# CursorKeypad.net
KiCad netlist of a schematic drawn in EAGLE
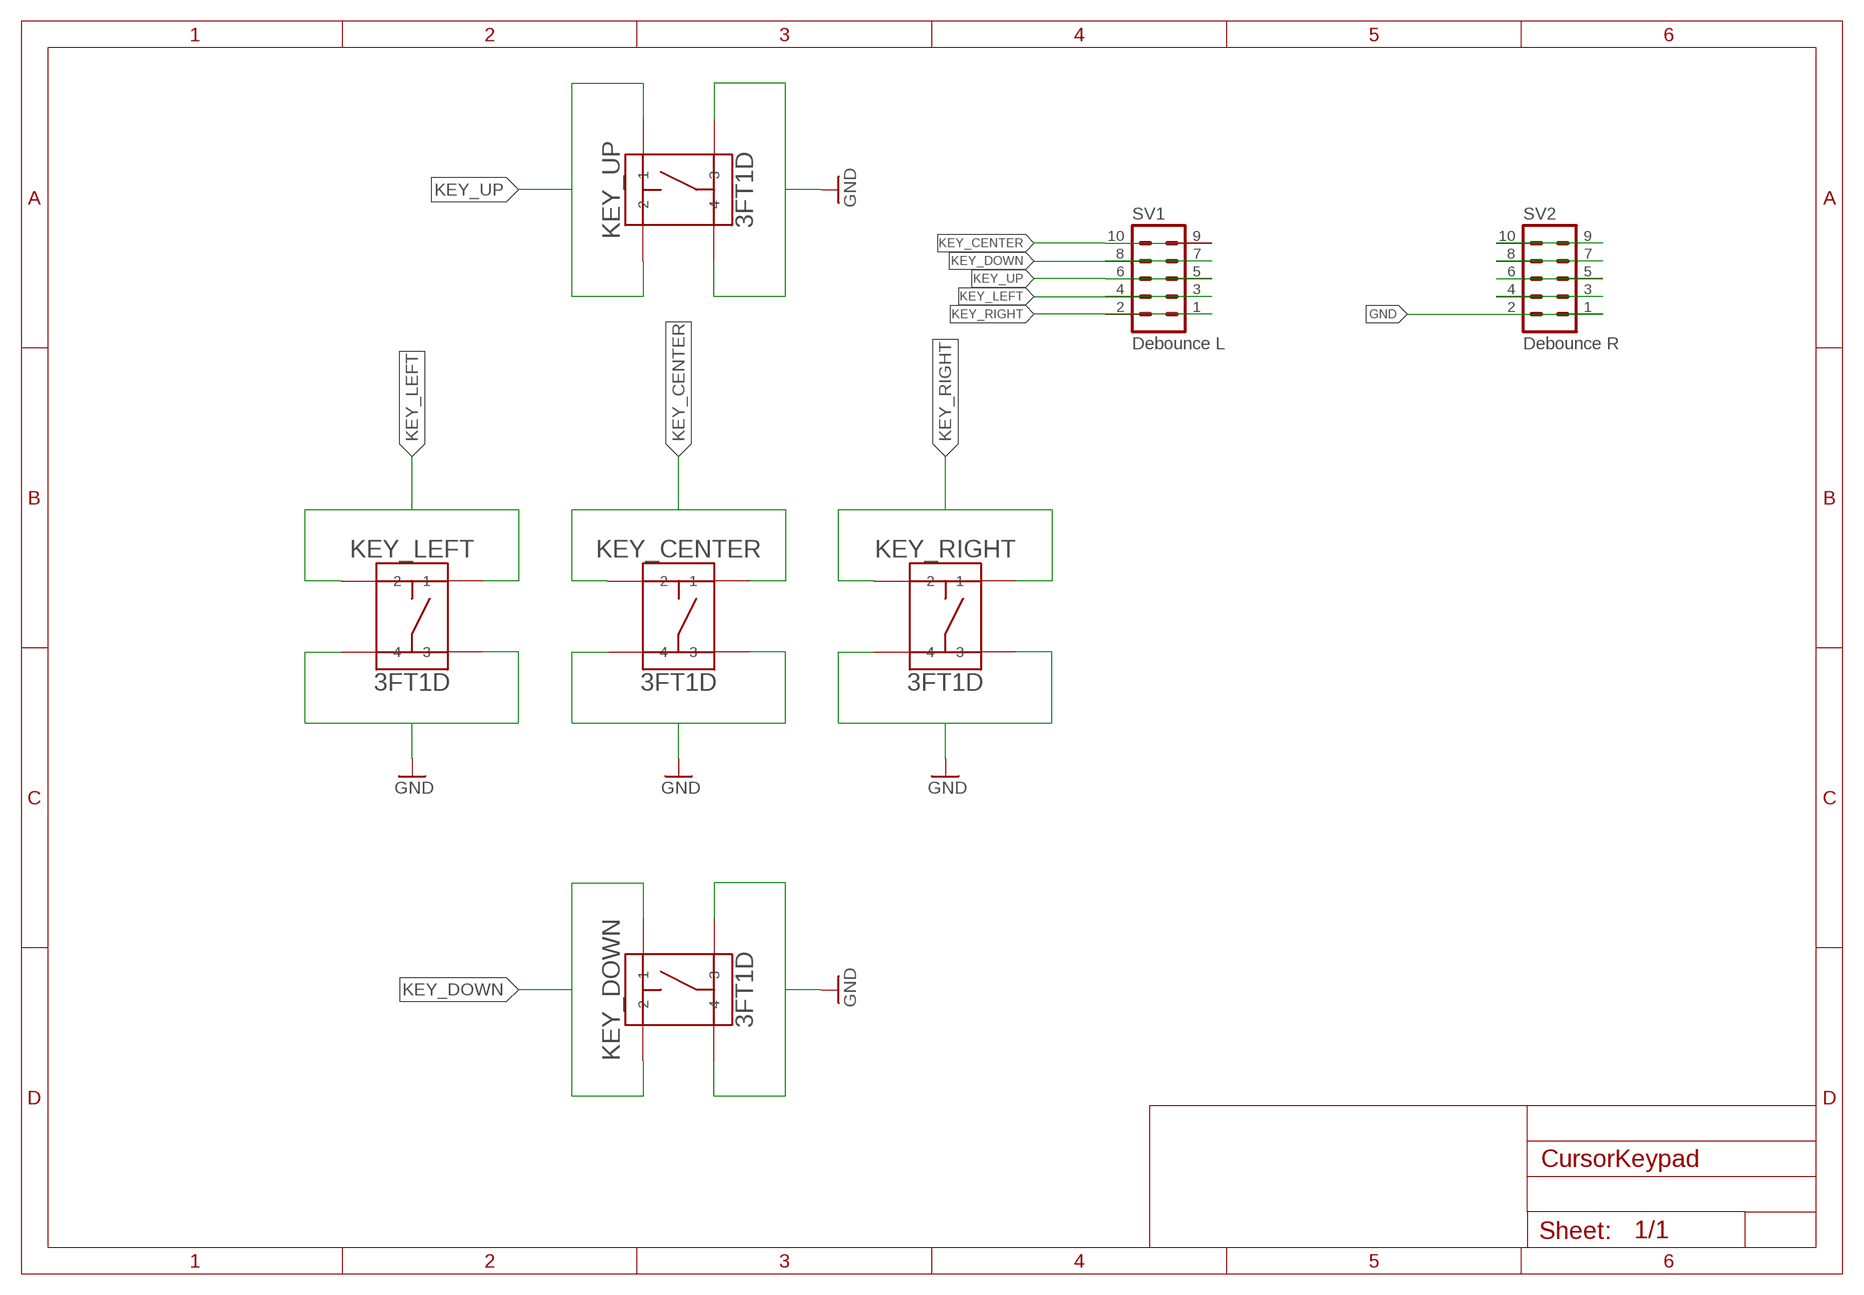
[diagram p0: schematic, sheet 1]

(export (version "E")
  (design (tool "Eeschema 10.0.6"))
  (components
    (comp (ref "KEY_CENTER")
      (value "3FT1D")
      (footprint "eagle-import:3FT")
      (libsource (lib "eagle-import") (part "3FT1D"))
    )
    (comp (ref "KEY_DOWN")
      (value "3FT1D")
      (footprint "eagle-import:3FT")
      (libsource (lib "eagle-import") (part "3FT1D"))
    )
    (comp (ref "KEY_LEFT")
      (value "3FT1D")
      (footprint "eagle-import:3FT")
      (libsource (lib "eagle-import") (part "3FT1D"))
    )
    (comp (ref "KEY_RIGHT")
      (value "3FT1D")
      (footprint "eagle-import:3FT")
      (libsource (lib "eagle-import") (part "3FT1D"))
    )
    (comp (ref "KEY_UP")
      (value "3FT1D")
      (footprint "eagle-import:3FT")
      (libsource (lib "eagle-import") (part "3FT1D"))
    )
    (comp (ref "SV1")
      (value "Debounce L")
      (footprint "eagle-import:MA05-2")
      (libsource (lib "eagle-import") (part "MA05-2"))
    )
    (comp (ref "SV2")
      (value "Debounce R")
      (footprint "eagle-import:MA05-2")
      (libsource (lib "eagle-import") (part "MA05-2"))
    )
  )
  (nets
    (net (code "1") (name "GND") (class "Default")
      (node (ref "KEY_CENTER") (pin "P$3") (pinfunction "3_P$3") (pintype "bidirectional"))
      (node (ref "KEY_CENTER") (pin "P$4") (pinfunction "4_P$4") (pintype "bidirectional"))
      (node (ref "KEY_DOWN") (pin "P$3") (pinfunction "3_P$3") (pintype "bidirectional"))
      (node (ref "KEY_DOWN") (pin "P$4") (pinfunction "4_P$4") (pintype "bidirectional"))
      (node (ref "KEY_LEFT") (pin "P$3") (pinfunction "3_P$3") (pintype "bidirectional"))
      (node (ref "KEY_LEFT") (pin "P$4") (pinfunction "4_P$4") (pintype "bidirectional"))
      (node (ref "KEY_RIGHT") (pin "P$3") (pinfunction "3_P$3") (pintype "bidirectional"))
      (node (ref "KEY_RIGHT") (pin "P$4") (pinfunction "4_P$4") (pintype "bidirectional"))
      (node (ref "KEY_UP") (pin "P$3") (pinfunction "3_P$3") (pintype "bidirectional"))
      (node (ref "KEY_UP") (pin "P$4") (pinfunction "4_P$4") (pintype "bidirectional"))
      (node (ref "SV2") (pin "1") (pinfunction "1_1") (pintype "passive"))
      (node (ref "SV2") (pin "2") (pinfunction "2_2") (pintype "passive"))
    )
    (net (code "2") (name "KEY_CENTER") (class "Default")
      (node (ref "KEY_CENTER") (pin "P$1") (pinfunction "1_P$1") (pintype "bidirectional"))
      (node (ref "KEY_CENTER") (pin "P$2") (pinfunction "2_P$2") (pintype "bidirectional"))
      (node (ref "SV1") (pin "10") (pinfunction "10_10") (pintype "passive"))
      (node (ref "SV1") (pin "9") (pinfunction "9_9") (pintype "passive"))
    )
    (net (code "3") (name "KEY_DOWN") (class "Default")
      (node (ref "KEY_DOWN") (pin "P$1") (pinfunction "1_P$1") (pintype "bidirectional"))
      (node (ref "KEY_DOWN") (pin "P$2") (pinfunction "2_P$2") (pintype "bidirectional"))
      (node (ref "SV1") (pin "7") (pinfunction "7_7") (pintype "passive"))
      (node (ref "SV1") (pin "8") (pinfunction "8_8") (pintype "passive"))
    )
    (net (code "4") (name "KEY_LEFT") (class "Default")
      (node (ref "KEY_LEFT") (pin "P$1") (pinfunction "1_P$1") (pintype "bidirectional"))
      (node (ref "KEY_LEFT") (pin "P$2") (pinfunction "2_P$2") (pintype "bidirectional"))
      (node (ref "SV1") (pin "3") (pinfunction "3_3") (pintype "passive"))
      (node (ref "SV1") (pin "4") (pinfunction "4_4") (pintype "passive"))
    )
    (net (code "5") (name "KEY_RIGHT") (class "Default")
      (node (ref "KEY_RIGHT") (pin "P$1") (pinfunction "1_P$1") (pintype "bidirectional"))
      (node (ref "KEY_RIGHT") (pin "P$2") (pinfunction "2_P$2") (pintype "bidirectional"))
      (node (ref "SV1") (pin "1") (pinfunction "1_1") (pintype "passive"))
      (node (ref "SV1") (pin "2") (pinfunction "2_2") (pintype "passive"))
    )
    (net (code "6") (name "KEY_UP") (class "Default")
      (node (ref "KEY_UP") (pin "P$1") (pinfunction "1_P$1") (pintype "bidirectional"))
      (node (ref "KEY_UP") (pin "P$2") (pinfunction "2_P$2") (pintype "bidirectional"))
      (node (ref "SV1") (pin "5") (pinfunction "5_5") (pintype "passive"))
      (node (ref "SV1") (pin "6") (pinfunction "6_6") (pintype "passive"))
    )
    (net (code "7") (name "Net-(SV2-Pad3)") (class "Default")
      (node (ref "SV2") (pin "3") (pinfunction "3_3") (pintype "passive"))
      (node (ref "SV2") (pin "4") (pinfunction "4_4") (pintype "passive"))
    )
    (net (code "8") (name "Net-(SV2-Pad5)") (class "Default")
      (node (ref "SV2") (pin "5") (pinfunction "5_5") (pintype "passive"))
      (node (ref "SV2") (pin "6") (pinfunction "6_6") (pintype "passive"))
    )
    (net (code "9") (name "Net-(SV2-Pad7)") (class "Default")
      (node (ref "SV2") (pin "7") (pinfunction "7_7") (pintype "passive"))
      (node (ref "SV2") (pin "8") (pinfunction "8_8") (pintype "passive"))
    )
    (net (code "10") (name "Net-(SV2-Pad10)") (class "Default")
      (node (ref "SV2") (pin "10") (pinfunction "10_10") (pintype "passive"))
      (node (ref "SV2") (pin "9") (pinfunction "9_9") (pintype "passive"))
    )
  )
)
